# ui_board.net
KiCad netlist of a schematic drawn in EAGLE
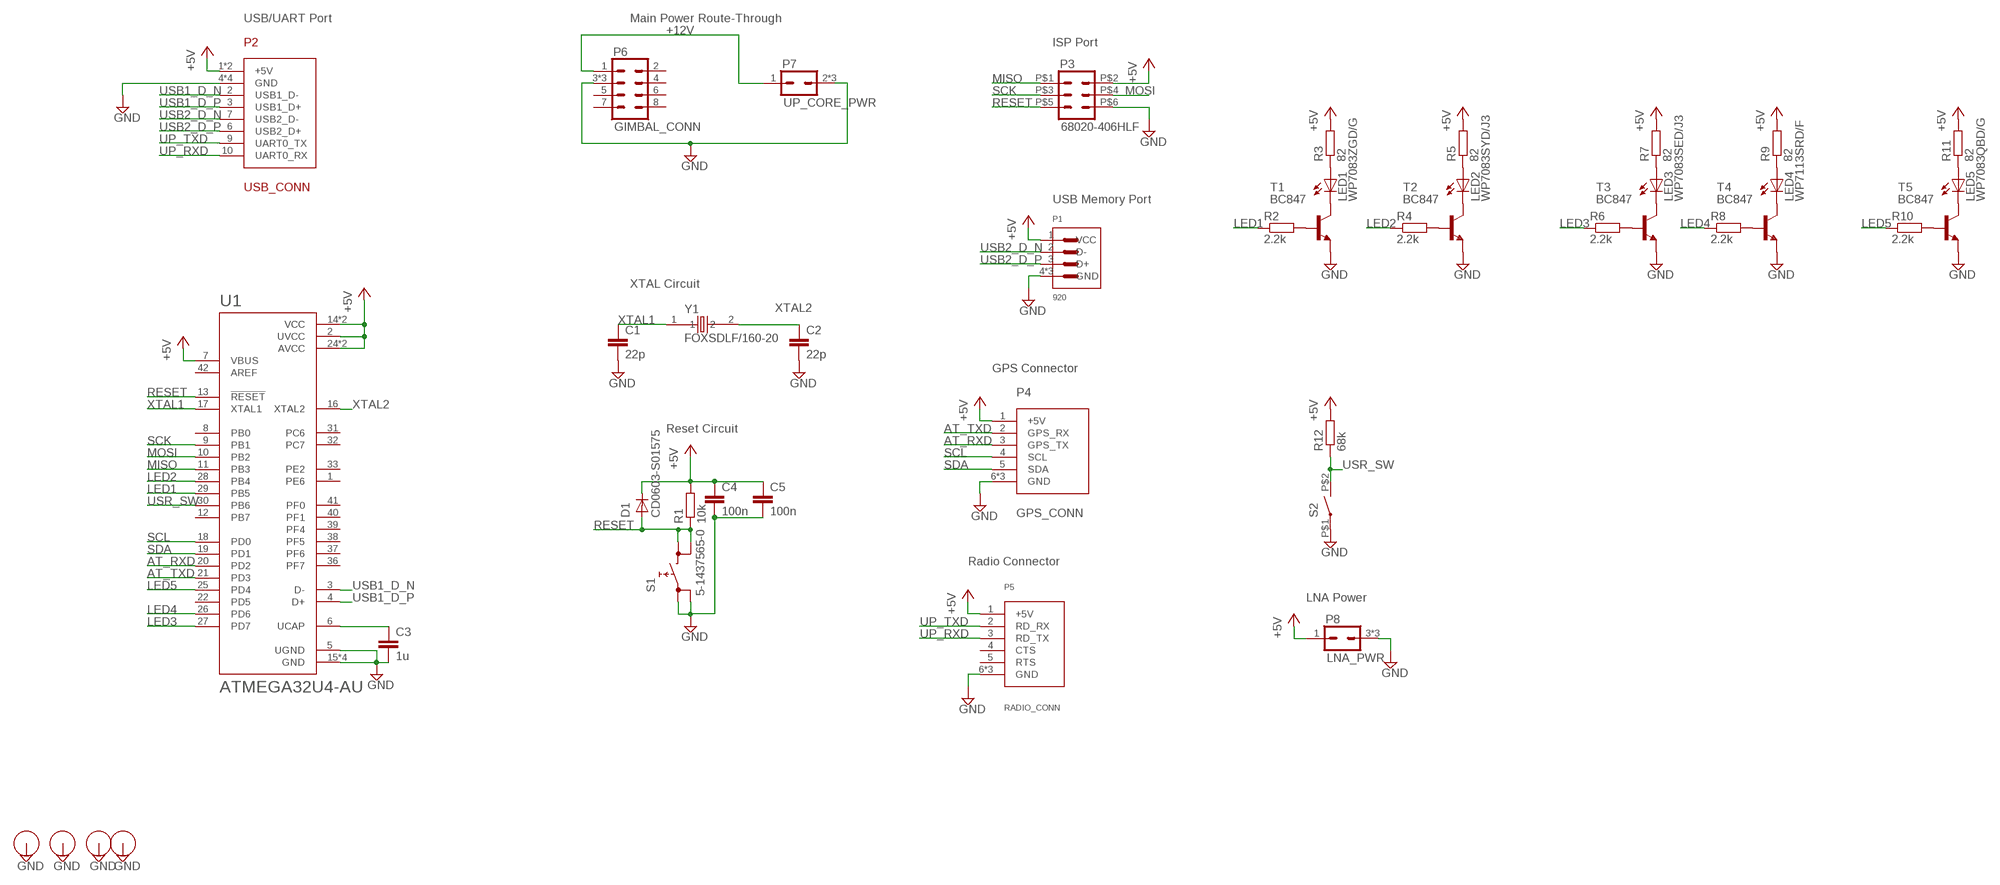
[diagram p0: schematic, sheet 1]

(export (version "E")
  (design (tool "Eeschema 10.0.6"))
  (components
    (comp (ref "C1")
      (value "22p")
      (footprint "eagle-import:C0805")
      (libsource (lib "eagle-import") (part "resistor_348_C-EUC0805"))
    )
    (comp (ref "C2")
      (value "22p")
      (footprint "eagle-import:C0805")
      (libsource (lib "eagle-import") (part "resistor_348_C-EUC0805"))
    )
    (comp (ref "C3")
      (value "1u")
      (footprint "eagle-import:C0805")
      (libsource (lib "eagle-import") (part "C-EUC0805"))
    )
    (comp (ref "C4")
      (value "100n")
      (footprint "eagle-import:C0805")
      (libsource (lib "eagle-import") (part "C-EUC0805"))
    )
    (comp (ref "C5")
      (value "100n")
      (footprint "eagle-import:C0805")
      (libsource (lib "eagle-import") (part "C-EUC0805"))
    )
    (comp (ref "D1")
      (value "CD0603-S01575")
      (footprint "eagle-import:D0603")
      (libsource (lib "eagle-import") (part "CD0603-S01575"))
    )
    (comp (ref "LED1")
      (value "WP7083ZGD/G")
      (footprint "eagle-import:LED5MM")
      (libsource (lib "eagle-import") (part "LED5MM"))
    )
    (comp (ref "LED2")
      (value "WP7083SYD/J3")
      (footprint "eagle-import:LED5MM")
      (libsource (lib "eagle-import") (part "LED5MM"))
    )
    (comp (ref "LED3")
      (value "WP7083SED/J3")
      (footprint "eagle-import:LED5MM")
      (libsource (lib "eagle-import") (part "LED5MM"))
    )
    (comp (ref "LED4")
      (value "WP7113SRD/F")
      (footprint "eagle-import:LED5MM")
      (libsource (lib "eagle-import") (part "LED5MM"))
    )
    (comp (ref "LED5")
      (value "WP7083QBD/G")
      (footprint "eagle-import:LED5MM")
      (libsource (lib "eagle-import") (part "LED5MM"))
    )
    (comp (ref "P1")
      (value "920")
      (footprint "eagle-import:USB_THRU")
      (libsource (lib "eagle-import") (part "920"))
    )
    (comp (ref "P2")
      (value "USB_CONN")
      (footprint "eagle-import:SM10B-SRSS-TB")
      (libsource (lib "eagle-import") (part "USB_CONN"))
    )
    (comp (ref "P3")
      (value "68020-406HLF")
      (footprint "eagle-import:2X3_THRU")
      (libsource (lib "eagle-import") (part "68020-406HLF"))
    )
    (comp (ref "P4")
      (value "GPS_CONN")
      (footprint "eagle-import:SM06B-GHS-TB")
      (libsource (lib "eagle-import") (part "GPS_CONN"))
    )
    (comp (ref "P5")
      (value "RADIO_CONN")
      (footprint "eagle-import:DF13C-6P-1.25V")
      (libsource (lib "eagle-import") (part "RADIO_CONN"))
    )
    (comp (ref "P6")
      (value "GIMBAL_CONN")
      (footprint "eagle-import:GIMBAL_CONN")
      (libsource (lib "eagle-import") (part "GIMBAL_CONN"))
    )
    (comp (ref "P7")
      (value "UP_CORE_PWR")
      (footprint "eagle-import:SM02B-GHS-TB")
      (libsource (lib "eagle-import") (part "UP_CORE_PWR"))
    )
    (comp (ref "P8")
      (value "LNA_PWR")
      (footprint "eagle-import:SM03B-GHS-TB")
      (libsource (lib "eagle-import") (part "LNA_PWR"))
    )
    (comp (ref "R1")
      (value "10k")
      (footprint "eagle-import:R0805")
      (libsource (lib "eagle-import") (part "R-EU_R0805"))
    )
    (comp (ref "R2")
      (value "2.2k")
      (footprint "eagle-import:R0805")
      (libsource (lib "eagle-import") (part "R-EU_R0805"))
    )
    (comp (ref "R3")
      (value "82")
      (footprint "eagle-import:R0805")
      (libsource (lib "eagle-import") (part "R-EU_R0805"))
    )
    (comp (ref "R4")
      (value "2.2k")
      (footprint "eagle-import:R0805")
      (libsource (lib "eagle-import") (part "R-EU_R0805"))
    )
    (comp (ref "R5")
      (value "82")
      (footprint "eagle-import:R0805")
      (libsource (lib "eagle-import") (part "R-EU_R0805"))
    )
    (comp (ref "R6")
      (value "2.2k")
      (footprint "eagle-import:R0805")
      (libsource (lib "eagle-import") (part "R-EU_R0805"))
    )
    (comp (ref "R7")
      (value "82")
      (footprint "eagle-import:R0805")
      (libsource (lib "eagle-import") (part "R-EU_R0805"))
    )
    (comp (ref "R8")
      (value "2.2k")
      (footprint "eagle-import:R0805")
      (libsource (lib "eagle-import") (part "R-EU_R0805"))
    )
    (comp (ref "R9")
      (value "82")
      (footprint "eagle-import:R0805")
      (libsource (lib "eagle-import") (part "R-EU_R0805"))
    )
    (comp (ref "R10")
      (value "2.2k")
      (footprint "eagle-import:R0805")
      (libsource (lib "eagle-import") (part "R-EU_R0805"))
    )
    (comp (ref "R11")
      (value "82")
      (footprint "eagle-import:R0805")
      (libsource (lib "eagle-import") (part "R-EU_R0805"))
    )
    (comp (ref "R12")
      (value "68k")
      (footprint "eagle-import:R0805")
      (libsource (lib "eagle-import") (part "R-EU_R0805"))
    )
    (comp (ref "S1")
      (value "5-1437565-0")
      (footprint "eagle-import:5-1437565-0")
      (libsource (lib "eagle-import") (part "5-1437565-0"))
    )
    (comp (ref "S2")
      (value "2267078-1")
      (footprint "eagle-import:2267078-1")
      (libsource (lib "eagle-import") (part "2267078-1"))
    )
    (comp (ref "T1")
      (value "BC847")
      (footprint "eagle-import:SOT23")
      (libsource (lib "eagle-import") (part "BC847"))
    )
    (comp (ref "T2")
      (value "BC847")
      (footprint "eagle-import:SOT23")
      (libsource (lib "eagle-import") (part "BC847"))
    )
    (comp (ref "T3")
      (value "BC847")
      (footprint "eagle-import:SOT23")
      (libsource (lib "eagle-import") (part "BC847"))
    )
    (comp (ref "T4")
      (value "BC847")
      (footprint "eagle-import:SOT23")
      (libsource (lib "eagle-import") (part "BC847"))
    )
    (comp (ref "T5")
      (value "BC847")
      (footprint "eagle-import:SOT23")
      (libsource (lib "eagle-import") (part "BC847"))
    )
    (comp (ref "U$1")
      (value "MOUNT_PAD")
      (footprint "eagle-import:MOUNT_PAD")
      (libsource (lib "eagle-import") (part "MOUNT_PAD"))
    )
    (comp (ref "U$3")
      (value "MOUNT_PAD")
      (footprint "eagle-import:MOUNT_PAD")
      (libsource (lib "eagle-import") (part "MOUNT_PAD"))
    )
    (comp (ref "U$4")
      (value "MOUNT_PAD")
      (footprint "eagle-import:MOUNT_PAD")
      (libsource (lib "eagle-import") (part "MOUNT_PAD"))
    )
    (comp (ref "U$5")
      (value "MOUNT_PAD")
      (footprint "eagle-import:MOUNT_PAD")
      (libsource (lib "eagle-import") (part "MOUNT_PAD"))
    )
    (comp (ref "U1")
      (value "ATMEGA32U4-AU")
      (footprint "eagle-import:QFP80P1200X1200X120-44N")
      (fields (field (name "MANUFACTURER") "Atmel"))
      (libsource (lib "eagle-import") (part "ATMEGA32U4-AU"))
    )
    (comp (ref "Y1")
      (value "FOXSDLF/160-20")
      (footprint "eagle-import:XTAL1170X500X450")
      (fields (field (name "MANUFACTURER") "Fox Electronics"))
      (libsource (lib "eagle-import") (part "FOXSDLF/160-20"))
    )
  )
  (nets
    (net (code "1") (name "+5V") (class "Default")
      (node (ref "C4") (pin "1") (pinfunction "1_1") (pintype "passive"))
      (node (ref "C5") (pin "1") (pinfunction "1_1") (pintype "passive"))
      (node (ref "D1") (pin "P$1") (pinfunction "C_P$1") (pintype "passive"))
      (node (ref "P1") (pin "1") (pinfunction "VCC_1") (pintype "power_in"))
      (node (ref "P2") (pin "1") (pinfunction "+5V_1") (pintype "power_in"))
      (node (ref "P2") (pin "5") (pinfunction "+5V_5") (pintype "power_in"))
      (node (ref "P3") (pin "P$2") (pinfunction "2_P$2") (pintype "bidirectional"))
      (node (ref "P4") (pin "1") (pinfunction "+5V_1") (pintype "power_in"))
      (node (ref "P5") (pin "1") (pinfunction "+5V_1") (pintype "power_in"))
      (node (ref "P8") (pin "1") (pinfunction "1_1") (pintype "bidirectional"))
      (node (ref "R1") (pin "2") (pinfunction "2_2") (pintype "passive"))
      (node (ref "R11") (pin "2") (pinfunction "2_2") (pintype "passive"))
      (node (ref "R12") (pin "2") (pinfunction "2_2") (pintype "passive"))
      (node (ref "R3") (pin "2") (pinfunction "2_2") (pintype "passive"))
      (node (ref "R5") (pin "2") (pinfunction "2_2") (pintype "passive"))
      (node (ref "R7") (pin "2") (pinfunction "2_2") (pintype "passive"))
      (node (ref "R9") (pin "2") (pinfunction "2_2") (pintype "passive"))
      (node (ref "U1") (pin "14") (pinfunction "VCC_14") (pintype "power_in"))
      (node (ref "U1") (pin "2") (pinfunction "UVCC_2") (pintype "power_in"))
      (node (ref "U1") (pin "24") (pinfunction "AVCC_24") (pintype "power_in"))
      (node (ref "U1") (pin "34") (pinfunction "VCC_34") (pintype "power_in"))
      (node (ref "U1") (pin "44") (pinfunction "AVCC_44") (pintype "power_in"))
      (node (ref "U1") (pin "7") (pinfunction "VBUS_7") (pintype "input"))
    )
    (net (code "2") (name "/+12V") (class "Default")
      (node (ref "P6") (pin "1") (pinfunction "1_1") (pintype "bidirectional"))
      (node (ref "P7") (pin "1") (pinfunction "1_1") (pintype "bidirectional"))
    )
    (net (code "3") (name "/AT_RXD") (class "Default")
      (node (ref "P4") (pin "3") (pinfunction "GPS_TX_3") (pintype "output"))
      (node (ref "U1") (pin "20") (pinfunction "PD2_20") (pintype "bidirectional"))
    )
    (net (code "4") (name "/AT_TXD") (class "Default")
      (node (ref "P4") (pin "2") (pinfunction "GPS_RX_2") (pintype "input"))
      (node (ref "U1") (pin "21") (pinfunction "PD3_21") (pintype "bidirectional"))
    )
    (net (code "5") (name "/LED1") (class "Default")
      (node (ref "R2") (pin "1") (pinfunction "1_1") (pintype "passive"))
      (node (ref "U1") (pin "29") (pinfunction "PB5_29") (pintype "bidirectional"))
    )
    (net (code "6") (name "/LED2") (class "Default")
      (node (ref "R4") (pin "1") (pinfunction "1_1") (pintype "passive"))
      (node (ref "U1") (pin "28") (pinfunction "PB4_28") (pintype "bidirectional"))
    )
    (net (code "7") (name "/LED3") (class "Default")
      (node (ref "R6") (pin "1") (pinfunction "1_1") (pintype "passive"))
      (node (ref "U1") (pin "27") (pinfunction "PD7_27") (pintype "bidirectional"))
    )
    (net (code "8") (name "/LED4") (class "Default")
      (node (ref "R8") (pin "1") (pinfunction "1_1") (pintype "passive"))
      (node (ref "U1") (pin "26") (pinfunction "PD6_26") (pintype "bidirectional"))
    )
    (net (code "9") (name "/LED5") (class "Default")
      (node (ref "R10") (pin "1") (pinfunction "1_1") (pintype "passive"))
      (node (ref "U1") (pin "25") (pinfunction "PD4_25") (pintype "bidirectional"))
    )
    (net (code "10") (name "/MISO") (class "Default")
      (node (ref "P3") (pin "P$1") (pinfunction "1_P$1") (pintype "bidirectional"))
      (node (ref "U1") (pin "11") (pinfunction "PB3_11") (pintype "bidirectional"))
    )
    (net (code "11") (name "/MOSI") (class "Default")
      (node (ref "P3") (pin "P$4") (pinfunction "4_P$4") (pintype "bidirectional"))
      (node (ref "U1") (pin "10") (pinfunction "PB2_10") (pintype "bidirectional"))
    )
    (net (code "12") (name "/RESET") (class "Default")
      (node (ref "D1") (pin "P$2") (pinfunction "A_P$2") (pintype "passive"))
      (node (ref "P3") (pin "P$5") (pinfunction "5_P$5") (pintype "bidirectional"))
      (node (ref "R1") (pin "1") (pinfunction "1_1") (pintype "passive"))
      (node (ref "S1") (pin "P$3") (pinfunction "1_P$3") (pintype "passive"))
      (node (ref "S1") (pin "P$4") (pinfunction "1_P$4") (pintype "passive"))
      (node (ref "U1") (pin "13") (pinfunction "~{RESET}_13") (pintype "input"))
    )
    (net (code "13") (name "/SCK") (class "Default")
      (node (ref "P3") (pin "P$3") (pinfunction "3_P$3") (pintype "bidirectional"))
      (node (ref "U1") (pin "9") (pinfunction "PB1_9") (pintype "bidirectional"))
    )
    (net (code "14") (name "/SCL") (class "Default")
      (node (ref "P4") (pin "4") (pinfunction "SCL_4") (pintype "output"))
      (node (ref "U1") (pin "18") (pinfunction "PD0_18") (pintype "bidirectional"))
    )
    (net (code "15") (name "/SDA") (class "Default")
      (node (ref "P4") (pin "5") (pinfunction "SDA_5") (pintype "bidirectional"))
      (node (ref "U1") (pin "19") (pinfunction "PD1_19") (pintype "bidirectional"))
    )
    (net (code "16") (name "/UP_RXD") (class "Default")
      (node (ref "P2") (pin "10") (pinfunction "UART0_RX_10") (pintype "input"))
      (node (ref "P5") (pin "3") (pinfunction "RD_TX_3") (pintype "output"))
    )
    (net (code "17") (name "/UP_TXD") (class "Default")
      (node (ref "P2") (pin "9") (pinfunction "UART0_TX_9") (pintype "output"))
      (node (ref "P5") (pin "2") (pinfunction "RD_RX_2") (pintype "input"))
    )
    (net (code "18") (name "/USB1_D_N") (class "Default")
      (node (ref "P2") (pin "2") (pinfunction "USB1_D-_2") (pintype "bidirectional"))
      (node (ref "U1") (pin "3") (pinfunction "D-_3") (pintype "bidirectional"))
    )
    (net (code "19") (name "/USB1_D_P") (class "Default")
      (node (ref "P2") (pin "3") (pinfunction "USB1_D+_3") (pintype "bidirectional"))
      (node (ref "U1") (pin "4") (pinfunction "D+_4") (pintype "bidirectional"))
    )
    (net (code "20") (name "/USB2_D_N") (class "Default")
      (node (ref "P1") (pin "2") (pinfunction "D-_2") (pintype "bidirectional"))
      (node (ref "P2") (pin "7") (pinfunction "USB2_D-_7") (pintype "bidirectional"))
    )
    (net (code "21") (name "/USB2_D_P") (class "Default")
      (node (ref "P1") (pin "3") (pinfunction "D+_3") (pintype "bidirectional"))
      (node (ref "P2") (pin "6") (pinfunction "USB2_D+_6") (pintype "bidirectional"))
    )
    (net (code "22") (name "/USR_SW") (class "Default")
      (node (ref "R12") (pin "1") (pinfunction "1_1") (pintype "passive"))
      (node (ref "S2") (pin "P$2") (pinfunction "S_P$2") (pintype "passive"))
      (node (ref "U1") (pin "30") (pinfunction "PB6_30") (pintype "bidirectional"))
    )
    (net (code "23") (name "/XTAL1") (class "Default")
      (node (ref "C1") (pin "1") (pinfunction "1_1") (pintype "passive"))
      (node (ref "U1") (pin "17") (pinfunction "XTAL1_17") (pintype "input"))
      (node (ref "Y1") (pin "1") (pinfunction "1_1") (pintype "passive"))
    )
    (net (code "24") (name "/XTAL2") (class "Default")
      (node (ref "C2") (pin "1") (pinfunction "1_1") (pintype "passive"))
      (node (ref "U1") (pin "16") (pinfunction "XTAL2_16") (pintype "output"))
      (node (ref "Y1") (pin "2") (pinfunction "2_2") (pintype "passive"))
    )
    (net (code "25") (name "GND") (class "Default")
      (node (ref "C1") (pin "2") (pinfunction "2_2") (pintype "passive"))
      (node (ref "C2") (pin "2") (pinfunction "2_2") (pintype "passive"))
      (node (ref "C3") (pin "2") (pinfunction "2_2") (pintype "passive"))
      (node (ref "C4") (pin "2") (pinfunction "2_2") (pintype "passive"))
      (node (ref "C5") (pin "2") (pinfunction "2_2") (pintype "passive"))
      (node (ref "P1") (pin "4") (pinfunction "GND_4") (pintype "power_in"))
      (node (ref "P1") (pin "5") (pinfunction "GND_5") (pintype "power_in"))
      (node (ref "P1") (pin "6") (pinfunction "GND_6") (pintype "power_in"))
      (node (ref "P2") (pin "4") (pinfunction "GND_4") (pintype "power_in"))
      (node (ref "P2") (pin "8") (pinfunction "GND_8") (pintype "power_in"))
      (node (ref "P2") (pin "G1") (pinfunction "GND_G1") (pintype "power_in"))
      (node (ref "P2") (pin "G2") (pinfunction "GND_G2") (pintype "power_in"))
      (node (ref "P3") (pin "P$6") (pinfunction "6_P$6") (pintype "bidirectional"))
      (node (ref "P4") (pin "6") (pinfunction "GND_6") (pintype "power_in"))
      (node (ref "P4") (pin "G1") (pinfunction "GND_G1") (pintype "power_in"))
      (node (ref "P4") (pin "G2") (pinfunction "GND_G2") (pintype "power_in"))
      (node (ref "P5") (pin "6") (pinfunction "GND_6") (pintype "power_in"))
      (node (ref "P5") (pin "G1") (pinfunction "GND_G1") (pintype "power_in"))
      (node (ref "P5") (pin "G2") (pinfunction "GND_G2") (pintype "power_in"))
      (node (ref "P6") (pin "3") (pinfunction "3_3") (pintype "bidirectional"))
      (node (ref "P6") (pin "GND@1") (pinfunction "3_GND@1") (pintype "bidirectional"))
      (node (ref "P6") (pin "GND@2") (pinfunction "3_GND@2") (pintype "bidirectional"))
      (node (ref "P7") (pin "2") (pinfunction "2_2") (pintype "bidirectional"))
      (node (ref "P7") (pin "G1") (pinfunction "2_G1") (pintype "bidirectional"))
      (node (ref "P7") (pin "G2") (pinfunction "2_G2") (pintype "bidirectional"))
      (node (ref "P8") (pin "3") (pinfunction "2_3") (pintype "bidirectional"))
      (node (ref "P8") (pin "G1") (pinfunction "2_G1") (pintype "bidirectional"))
      (node (ref "P8") (pin "G2") (pinfunction "2_G2") (pintype "bidirectional"))
      (node (ref "S1") (pin "P$1") (pinfunction "0_P$1") (pintype "passive"))
      (node (ref "S1") (pin "P$2") (pinfunction "0_P$2") (pintype "passive"))
      (node (ref "S2") (pin "P$1") (pinfunction "P_P$1") (pintype "passive"))
      (node (ref "T1") (pin "2") (pinfunction "E_2") (pintype "passive"))
      (node (ref "T2") (pin "2") (pinfunction "E_2") (pintype "passive"))
      (node (ref "T3") (pin "2") (pinfunction "E_2") (pintype "passive"))
      (node (ref "T4") (pin "2") (pinfunction "E_2") (pintype "passive"))
      (node (ref "T5") (pin "2") (pinfunction "E_2") (pintype "passive"))
      (node (ref "U$1") (pin "P$1") (pinfunction "GND_P$1") (pintype "power_in"))
      (node (ref "U$3") (pin "P$1") (pinfunction "GND_P$1") (pintype "power_in"))
      (node (ref "U$4") (pin "P$1") (pinfunction "GND_P$1") (pintype "power_in"))
      (node (ref "U$5") (pin "P$1") (pinfunction "GND_P$1") (pintype "power_in"))
      (node (ref "U1") (pin "15") (pinfunction "GND_15") (pintype "power_in"))
      (node (ref "U1") (pin "23") (pinfunction "GND_23") (pintype "power_in"))
      (node (ref "U1") (pin "35") (pinfunction "GND_35") (pintype "power_in"))
      (node (ref "U1") (pin "43") (pinfunction "GND_43") (pintype "power_in"))
      (node (ref "U1") (pin "5") (pinfunction "UGND_5") (pintype "power_in"))
    )
    (net (code "26") (name "Net-(LED1-C)") (class "Default")
      (node (ref "LED1") (pin "K") (pinfunction "C_K") (pintype "passive"))
      (node (ref "T1") (pin "3") (pinfunction "C_3") (pintype "passive"))
    )
    (net (code "27") (name "Net-(LED1-PadA)") (class "Default")
      (node (ref "LED1") (pin "A") (pinfunction "A_A") (pintype "passive"))
      (node (ref "R3") (pin "1") (pinfunction "1_1") (pintype "passive"))
    )
    (net (code "28") (name "Net-(LED2-C)") (class "Default")
      (node (ref "LED2") (pin "K") (pinfunction "C_K") (pintype "passive"))
      (node (ref "T2") (pin "3") (pinfunction "C_3") (pintype "passive"))
    )
    (net (code "29") (name "Net-(LED2-PadA)") (class "Default")
      (node (ref "LED2") (pin "A") (pinfunction "A_A") (pintype "passive"))
      (node (ref "R5") (pin "1") (pinfunction "1_1") (pintype "passive"))
    )
    (net (code "30") (name "Net-(LED3-C)") (class "Default")
      (node (ref "LED3") (pin "K") (pinfunction "C_K") (pintype "passive"))
      (node (ref "T3") (pin "3") (pinfunction "C_3") (pintype "passive"))
    )
    (net (code "31") (name "Net-(LED3-PadA)") (class "Default")
      (node (ref "LED3") (pin "A") (pinfunction "A_A") (pintype "passive"))
      (node (ref "R7") (pin "1") (pinfunction "1_1") (pintype "passive"))
    )
    (net (code "32") (name "Net-(LED4-C)") (class "Default")
      (node (ref "LED4") (pin "K") (pinfunction "C_K") (pintype "passive"))
      (node (ref "T4") (pin "3") (pinfunction "C_3") (pintype "passive"))
    )
    (net (code "33") (name "Net-(LED4-PadA)") (class "Default")
      (node (ref "LED4") (pin "A") (pinfunction "A_A") (pintype "passive"))
      (node (ref "R9") (pin "1") (pinfunction "1_1") (pintype "passive"))
    )
    (net (code "34") (name "Net-(LED5-C)") (class "Default")
      (node (ref "LED5") (pin "K") (pinfunction "C_K") (pintype "passive"))
      (node (ref "T5") (pin "3") (pinfunction "C_3") (pintype "passive"))
    )
    (net (code "35") (name "Net-(LED5-PadA)") (class "Default")
      (node (ref "LED5") (pin "A") (pinfunction "A_A") (pintype "passive"))
      (node (ref "R11") (pin "1") (pinfunction "1_1") (pintype "passive"))
    )
    (net (code "36") (name "Net-(T1-B)") (class "Default")
      (node (ref "R2") (pin "2") (pinfunction "2_2") (pintype "passive"))
      (node (ref "T1") (pin "1") (pinfunction "B_1") (pintype "passive"))
    )
    (net (code "37") (name "Net-(T2-B)") (class "Default")
      (node (ref "R4") (pin "2") (pinfunction "2_2") (pintype "passive"))
      (node (ref "T2") (pin "1") (pinfunction "B_1") (pintype "passive"))
    )
    (net (code "38") (name "Net-(T3-B)") (class "Default")
      (node (ref "R6") (pin "2") (pinfunction "2_2") (pintype "passive"))
      (node (ref "T3") (pin "1") (pinfunction "B_1") (pintype "passive"))
    )
    (net (code "39") (name "Net-(T4-B)") (class "Default")
      (node (ref "R8") (pin "2") (pinfunction "2_2") (pintype "passive"))
      (node (ref "T4") (pin "1") (pinfunction "B_1") (pintype "passive"))
    )
    (net (code "40") (name "Net-(T5-B)") (class "Default")
      (node (ref "R10") (pin "2") (pinfunction "2_2") (pintype "passive"))
      (node (ref "T5") (pin "1") (pinfunction "B_1") (pintype "passive"))
    )
    (net (code "41") (name "Net-(U1-UCAP)") (class "Default")
      (node (ref "C3") (pin "1") (pinfunction "1_1") (pintype "passive"))
      (node (ref "U1") (pin "6") (pinfunction "UCAP_6") (pintype "passive"))
    )
    (net (code "42") (name "unconnected-(P5-CTS-Pad4)") (class "Default")
      (node (ref "P5") (pin "4") (pinfunction "CTS_4") (pintype "input"))
    )
    (net (code "43") (name "unconnected-(P5-RTS-Pad5)") (class "Default")
      (node (ref "P5") (pin "5") (pinfunction "RTS_5") (pintype "output"))
    )
    (net (code "44") (name "unconnected-(P6-Pad2)") (class "Default")
      (node (ref "P6") (pin "2") (pinfunction "2_2") (pintype "bidirectional"))
    )
    (net (code "45") (name "unconnected-(P6-Pad4)") (class "Default")
      (node (ref "P6") (pin "4") (pinfunction "4_4") (pintype "bidirectional"))
    )
    (net (code "46") (name "unconnected-(P6-Pad5)") (class "Default")
      (node (ref "P6") (pin "5") (pinfunction "5_5") (pintype "bidirectional"))
    )
    (net (code "47") (name "unconnected-(P6-Pad6)") (class "Default")
      (node (ref "P6") (pin "6") (pinfunction "6_6") (pintype "bidirectional"))
    )
    (net (code "48") (name "unconnected-(P6-Pad7)") (class "Default")
      (node (ref "P6") (pin "7") (pinfunction "7_7") (pintype "bidirectional"))
    )
    (net (code "49") (name "unconnected-(P6-Pad8)") (class "Default")
      (node (ref "P6") (pin "8") (pinfunction "8_8") (pintype "bidirectional"))
    )
    (net (code "50") (name "unconnected-(U1-AREF-Pad42)") (class "Default")
      (node (ref "U1") (pin "42") (pinfunction "AREF_42") (pintype "input"))
    )
    (net (code "51") (name "unconnected-(U1-PB0-Pad8)") (class "Default")
      (node (ref "U1") (pin "8") (pinfunction "PB0_8") (pintype "bidirectional"))
    )
    (net (code "52") (name "unconnected-(U1-PB7-Pad12)") (class "Default")
      (node (ref "U1") (pin "12") (pinfunction "PB7_12") (pintype "bidirectional"))
    )
    (net (code "53") (name "unconnected-(U1-PC6-Pad31)") (class "Default")
      (node (ref "U1") (pin "31") (pinfunction "PC6_31") (pintype "bidirectional"))
    )
    (net (code "54") (name "unconnected-(U1-PC7-Pad32)") (class "Default")
      (node (ref "U1") (pin "32") (pinfunction "PC7_32") (pintype "bidirectional"))
    )
    (net (code "55") (name "unconnected-(U1-PD5-Pad22)") (class "Default")
      (node (ref "U1") (pin "22") (pinfunction "PD5_22") (pintype "bidirectional"))
    )
    (net (code "56") (name "unconnected-(U1-PE2-Pad33)") (class "Default")
      (node (ref "U1") (pin "33") (pinfunction "PE2_33") (pintype "bidirectional"))
    )
    (net (code "57") (name "unconnected-(U1-PE6-Pad1)") (class "Default")
      (node (ref "U1") (pin "1") (pinfunction "PE6_1") (pintype "bidirectional"))
    )
    (net (code "58") (name "unconnected-(U1-PF0-Pad41)") (class "Default")
      (node (ref "U1") (pin "41") (pinfunction "PF0_41") (pintype "bidirectional"))
    )
    (net (code "59") (name "unconnected-(U1-PF1-Pad40)") (class "Default")
      (node (ref "U1") (pin "40") (pinfunction "PF1_40") (pintype "bidirectional"))
    )
    (net (code "60") (name "unconnected-(U1-PF4-Pad39)") (class "Default")
      (node (ref "U1") (pin "39") (pinfunction "PF4_39") (pintype "bidirectional"))
    )
    (net (code "61") (name "unconnected-(U1-PF5-Pad38)") (class "Default")
      (node (ref "U1") (pin "38") (pinfunction "PF5_38") (pintype "bidirectional"))
    )
    (net (code "62") (name "unconnected-(U1-PF6-Pad37)") (class "Default")
      (node (ref "U1") (pin "37") (pinfunction "PF6_37") (pintype "bidirectional"))
    )
    (net (code "63") (name "unconnected-(U1-PF7-Pad36)") (class "Default")
      (node (ref "U1") (pin "36") (pinfunction "PF7_36") (pintype "bidirectional"))
    )
  )
)
